# 1wire_slave.net
KiCad netlist of a schematic drawn in EAGLE
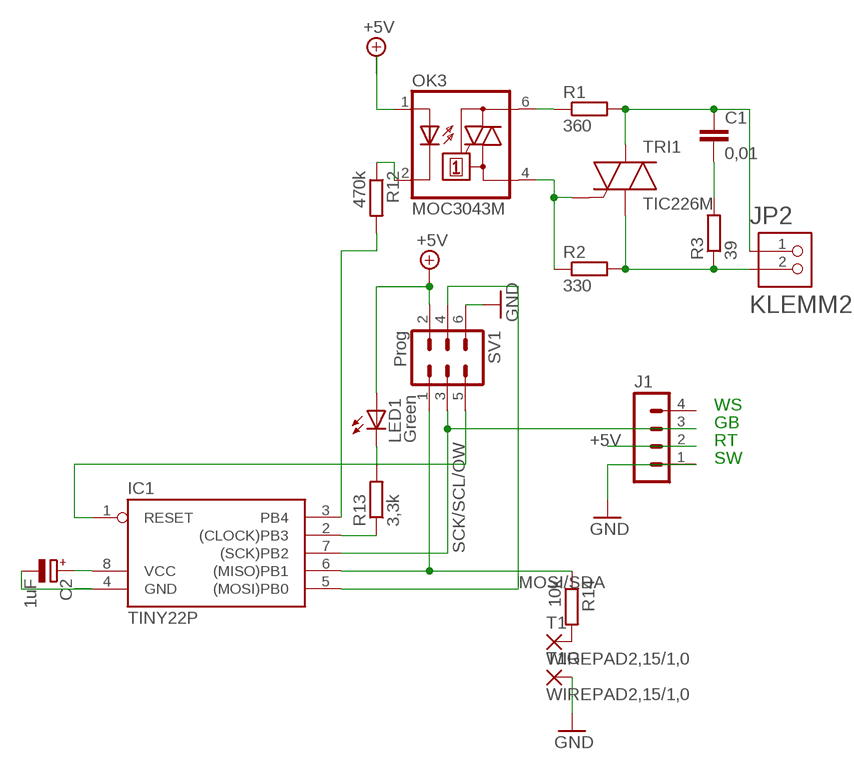
[diagram p0: schematic, sheet 1]

(export (version "E")
  (design (tool "Eeschema 10.0.6"))
  (components
    (comp (ref "C1")
      (value "0,01")
      (footprint "eagle-import:C15B6")
      (libsource (lib "eagle-import") (part "C15/6"))
    )
    (comp (ref "C2")
      (value "1uF")
      (footprint "eagle-import:E2,5-6E")
      (libsource (lib "eagle-import") (part "CPOL-EUE2,5-6E"))
    )
    (comp (ref "IC1")
      (value "TINY22P")
      (footprint "eagle-import:DIL08")
      (libsource (lib "eagle-import") (part "TINY22P"))
    )
    (comp (ref "J1")
      (value "MA04-1")
      (footprint "eagle-import:MA04-1")
      (libsource (lib "eagle-import") (part "MA04-1"))
    )
    (comp (ref "JP2")
      (value "KLEMM2")
      (footprint "eagle-import:KLEMM2")
      (libsource (lib "eagle-import") (part "KLEMM2"))
    )
    (comp (ref "LED1")
      (value "Green")
      (footprint "eagle-import:LED3MM")
      (libsource (lib "eagle-import") (part "LED3MM"))
    )
    (comp (ref "OK3")
      (value "MOC3043M")
      (footprint "eagle-import:DIL06")
      (fields (field (name "MF") "FAIRCHILD SEMICONDUCTOR") (field (name "MPN") "MOC3043-M"))
      (libsource (lib "eagle-import") (part "MOC3043M"))
    )
    (comp (ref "R1")
      (value "360")
      (footprint "eagle-import:0204_7")
      (libsource (lib "eagle-import") (part "resistor_R-EU_0204/7"))
    )
    (comp (ref "R2")
      (value "330")
      (footprint "eagle-import:0204_7")
      (libsource (lib "eagle-import") (part "resistor_R-EU_0204/7"))
    )
    (comp (ref "R3")
      (value "39")
      (footprint "eagle-import:0207_15")
      (libsource (lib "eagle-import") (part "resistor_R-EU_0207/15"))
    )
    (comp (ref "R12")
      (value "470k")
      (footprint "eagle-import:0207_12")
      (libsource (lib "eagle-import") (part "resistor_R-EU_0207/12"))
    )
    (comp (ref "R13")
      (value "3,3k")
      (footprint "eagle-import:0207_10")
      (libsource (lib "eagle-import") (part "resistor_R-EU_0207/10"))
    )
    (comp (ref "R14")
      (value "10k")
      (footprint "eagle-import:0204V")
      (libsource (lib "eagle-import") (part "R-EU_0204/2V"))
    )
    (comp (ref "SV1")
      (value "Prog")
      (footprint "eagle-import:MA03-2")
      (libsource (lib "eagle-import") (part "MA03-2"))
    )
    (comp (ref "T1")
      (value "WIREPAD2,15/1,0")
      (footprint "eagle-import:2,15_1,0")
      (libsource (lib "eagle-import") (part "WIREPAD2,15/1,0"))
    )
    (comp (ref "T1G")
      (value "WIREPAD2,15/1,0")
      (footprint "eagle-import:2,15_1,0")
      (libsource (lib "eagle-import") (part "WIREPAD2,15/1,0"))
    )
    (comp (ref "TRI1")
      (value "TIC226M")
      (footprint "eagle-import:TO-220A")
      (libsource (lib "eagle-import") (part "TIC226M"))
    )
  )
  (nets
    (net (code "1") (name "+5V") (class "Default")
      (node (ref "C2") (pin "+") (pinfunction "+_+") (pintype "passive"))
      (node (ref "IC1") (pin "8") (pinfunction "VCC_8") (pintype "power_in"))
      (node (ref "J1") (pin "2") (pinfunction "2_2") (pintype "passive"))
      (node (ref "LED1") (pin "A") (pinfunction "A_A") (pintype "passive"))
      (node (ref "OK3") (pin "1") (pinfunction "A_1") (pintype "passive"))
      (node (ref "SV1") (pin "2") (pinfunction "2_2") (pintype "passive"))
    )
    (net (code "2") (name "/MOSI{slash}SDA") (class "Default")
      (node (ref "IC1") (pin "5") (pinfunction "(MOSI)PB0_5") (pintype "bidirectional"))
      (node (ref "SV1") (pin "4") (pinfunction "4_4") (pintype "passive"))
    )
    (net (code "3") (name "/SCK{slash}SCL{slash}OW") (class "Default")
      (node (ref "IC1") (pin "7") (pinfunction "(SCK)PB2_7") (pintype "bidirectional"))
      (node (ref "J1") (pin "3") (pinfunction "3_3") (pintype "passive"))
      (node (ref "SV1") (pin "3") (pinfunction "3_3") (pintype "passive"))
    )
    (net (code "4") (name "GND") (class "Default")
      (node (ref "C2") (pin "-") (pinfunction "-_-") (pintype "passive"))
      (node (ref "IC1") (pin "4") (pinfunction "GND_4") (pintype "power_in"))
      (node (ref "J1") (pin "1") (pinfunction "1_1") (pintype "passive"))
      (node (ref "SV1") (pin "6") (pinfunction "6_6") (pintype "passive"))
      (node (ref "T1G") (pin "1") (pinfunction "P_1") (pintype "passive"))
    )
    (net (code "5") (name "Net-(C1-Pad2)") (class "Default")
      (node (ref "C1") (pin "2") (pinfunction "2_2") (pintype "passive"))
      (node (ref "R3") (pin "2") (pinfunction "2_2") (pintype "passive"))
    )
    (net (code "6") (name "Net-(IC1-(CLOCK)PB3)") (class "Default")
      (node (ref "IC1") (pin "2") (pinfunction "(CLOCK)PB3_2") (pintype "bidirectional"))
      (node (ref "R13") (pin "1") (pinfunction "1_1") (pintype "passive"))
    )
    (net (code "7") (name "Net-(IC1-(MISO)PB1)") (class "Default")
      (node (ref "IC1") (pin "6") (pinfunction "(MISO)PB1_6") (pintype "bidirectional"))
      (node (ref "R14") (pin "1") (pinfunction "1_1") (pintype "passive"))
      (node (ref "SV1") (pin "1") (pinfunction "1_1") (pintype "passive"))
    )
    (net (code "8") (name "Net-(IC1-PB4)") (class "Default")
      (node (ref "IC1") (pin "3") (pinfunction "PB4_3") (pintype "bidirectional"))
      (node (ref "R12") (pin "2") (pinfunction "2_2") (pintype "passive"))
    )
    (net (code "9") (name "Net-(IC1-RESET)") (class "Default")
      (node (ref "IC1") (pin "1") (pinfunction "RESET_1") (pintype "input"))
      (node (ref "SV1") (pin "5") (pinfunction "5_5") (pintype "passive"))
    )
    (net (code "10") (name "Net-(LED1-C)") (class "Default")
      (node (ref "LED1") (pin "K") (pinfunction "C_K") (pintype "passive"))
      (node (ref "R13") (pin "2") (pinfunction "2_2") (pintype "passive"))
    )
    (net (code "11") (name "Net-(OK3-A1)") (class "Default")
      (node (ref "OK3") (pin "4") (pinfunction "A1_4") (pintype "passive"))
      (node (ref "R2") (pin "1") (pinfunction "1_1") (pintype "passive"))
      (node (ref "TRI1") (pin "3") (pinfunction "G_3") (pintype "passive"))
    )
    (net (code "12") (name "Net-(OK3-A2)") (class "Default")
      (node (ref "OK3") (pin "6") (pinfunction "A2_6") (pintype "passive"))
      (node (ref "R1") (pin "1") (pinfunction "1_1") (pintype "passive"))
    )
    (net (code "13") (name "Net-(OK3-C)") (class "Default")
      (node (ref "OK3") (pin "2") (pinfunction "C_2") (pintype "passive"))
      (node (ref "R12") (pin "1") (pinfunction "1_1") (pintype "passive"))
    )
    (net (code "14") (name "Net-(T1-P)") (class "Default")
      (node (ref "R14") (pin "2") (pinfunction "2_2") (pintype "passive"))
      (node (ref "T1") (pin "1") (pinfunction "P_1") (pintype "passive"))
    )
    (net (code "15") (name "Net-(TRI1-A1)") (class "Default")
      (node (ref "JP2") (pin "2") (pinfunction "2_2") (pintype "passive"))
      (node (ref "R2") (pin "2") (pinfunction "2_2") (pintype "passive"))
      (node (ref "R3") (pin "1") (pinfunction "1_1") (pintype "passive"))
      (node (ref "TRI1") (pin "1") (pinfunction "A1_1") (pintype "passive"))
    )
    (net (code "16") (name "Net-(TRI1-A2)") (class "Default")
      (node (ref "C1") (pin "1") (pinfunction "1_1") (pintype "passive"))
      (node (ref "JP2") (pin "1") (pinfunction "1_1") (pintype "passive"))
      (node (ref "R1") (pin "2") (pinfunction "2_2") (pintype "passive"))
      (node (ref "TRI1") (pin "2") (pinfunction "A2_2") (pintype "passive"))
    )
    (net (code "17") (name "unconnected-(J1-Pad4)") (class "Default")
      (node (ref "J1") (pin "4") (pinfunction "4_4") (pintype "passive"))
    )
  )
)
